# Nixie_board.net
KiCad netlist of a schematic drawn in EAGLE
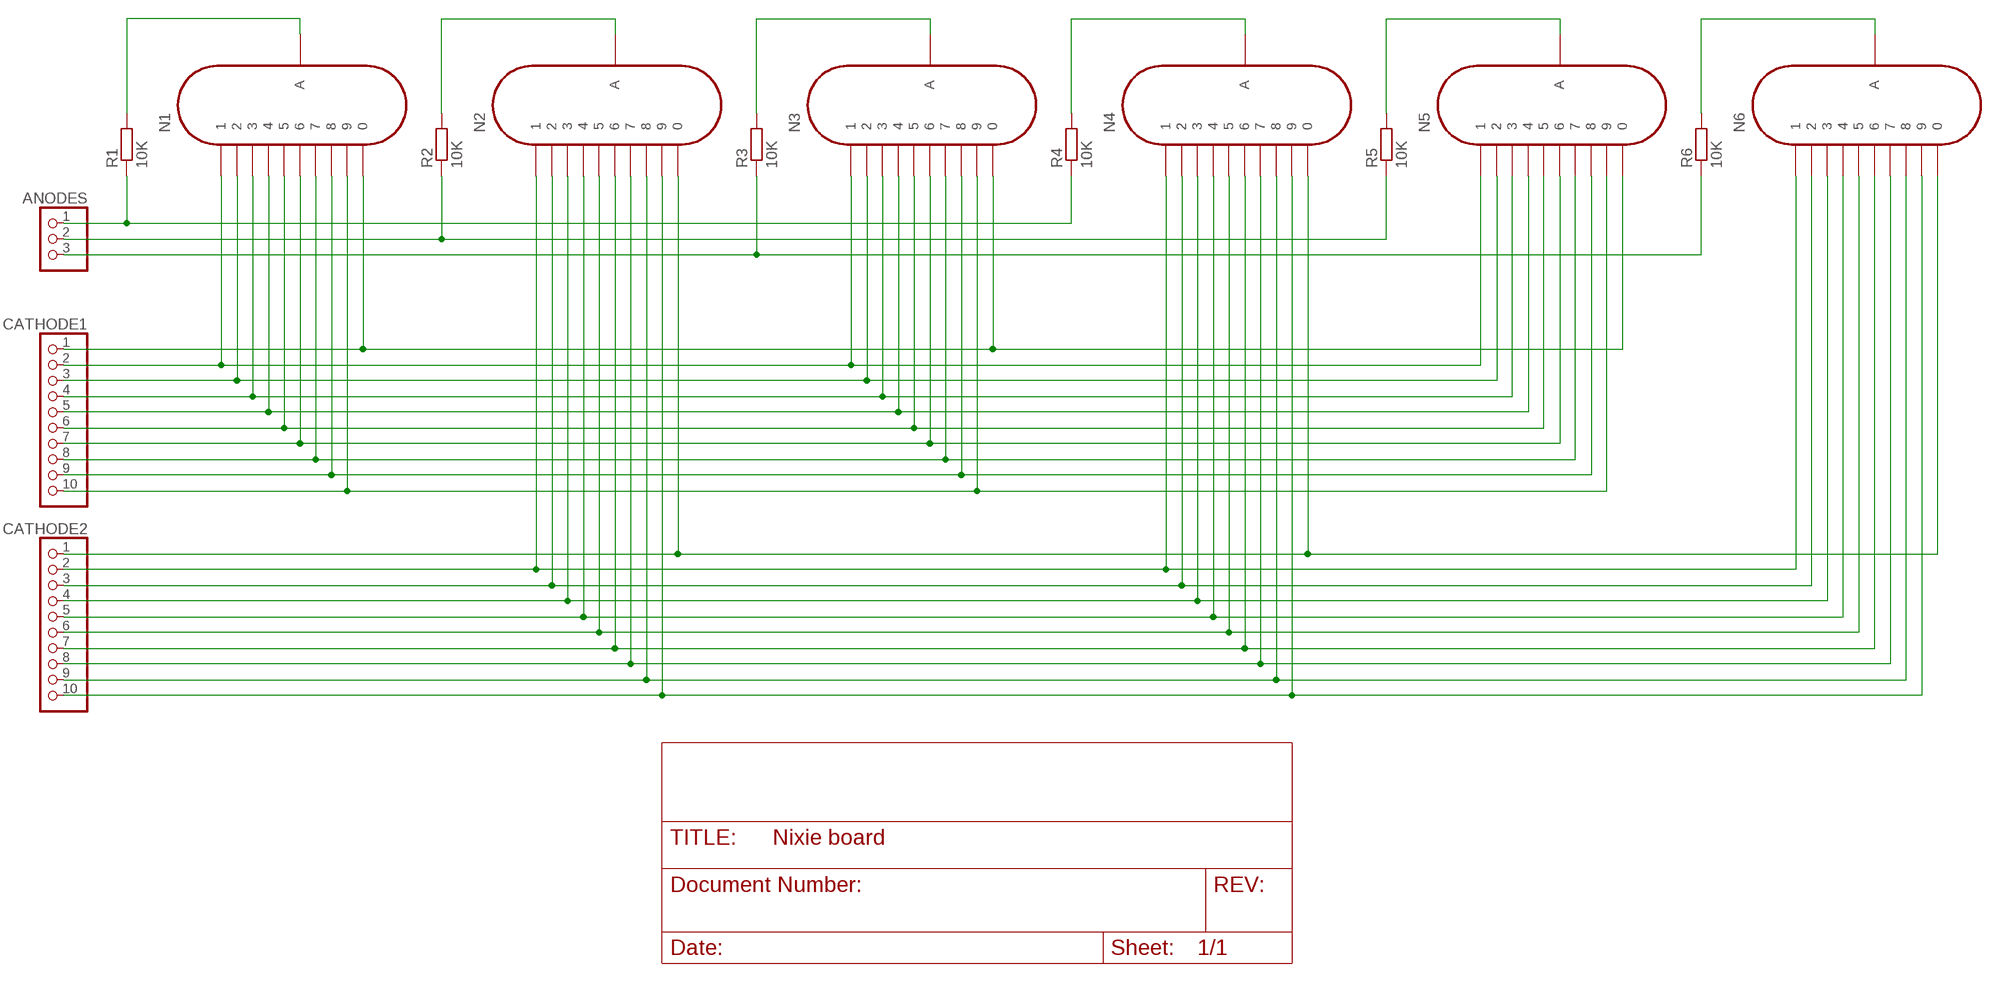
[diagram p0: schematic, sheet 1]

(export (version "E")
  (design (tool "Eeschema 10.0.6"))
  (components
    (comp (ref "ANODES")
      (value "PINHD-1X3")
      (footprint "eagle-import:1X03")
      (libsource (lib "eagle-import") (part "PINHD-1X3"))
    )
    (comp (ref "CATHODE1")
      (value "PINHD-1X10")
      (footprint "eagle-import:1X10")
      (libsource (lib "eagle-import") (part "PINHD-1X10"))
    )
    (comp (ref "CATHODE2")
      (value "PINHD-1X10")
      (footprint "eagle-import:1X10")
      (libsource (lib "eagle-import") (part "PINHD-1X10"))
    )
    (comp (ref "N1")
      (value "IN-12A")
      (footprint "eagle-import:IN-12")
      (libsource (lib "eagle-import") (part "IN-12A"))
    )
    (comp (ref "N2")
      (value "IN-12A")
      (footprint "eagle-import:IN-12")
      (libsource (lib "eagle-import") (part "IN-12A"))
    )
    (comp (ref "N3")
      (value "IN-12A")
      (footprint "eagle-import:IN-12")
      (libsource (lib "eagle-import") (part "IN-12A"))
    )
    (comp (ref "N4")
      (value "IN-12A")
      (footprint "eagle-import:IN-12")
      (libsource (lib "eagle-import") (part "IN-12A"))
    )
    (comp (ref "N5")
      (value "IN-12A")
      (footprint "eagle-import:IN-12")
      (libsource (lib "eagle-import") (part "IN-12A"))
    )
    (comp (ref "N6")
      (value "IN-12A")
      (footprint "eagle-import:IN-12")
      (libsource (lib "eagle-import") (part "IN-12A"))
    )
    (comp (ref "R1")
      (value "10K")
      (footprint "eagle-import:0207_10")
      (libsource (lib "eagle-import") (part "R-EU_0207/10"))
    )
    (comp (ref "R2")
      (value "10K")
      (footprint "eagle-import:0207_10")
      (libsource (lib "eagle-import") (part "R-EU_0207/10"))
    )
    (comp (ref "R3")
      (value "10K")
      (footprint "eagle-import:0207_10")
      (libsource (lib "eagle-import") (part "R-EU_0207/10"))
    )
    (comp (ref "R4")
      (value "10K")
      (footprint "eagle-import:0207_10")
      (libsource (lib "eagle-import") (part "R-EU_0207/10"))
    )
    (comp (ref "R5")
      (value "10K")
      (footprint "eagle-import:0207_10")
      (libsource (lib "eagle-import") (part "R-EU_0207/10"))
    )
    (comp (ref "R6")
      (value "10K")
      (footprint "eagle-import:0207_10")
      (libsource (lib "eagle-import") (part "R-EU_0207/10"))
    )
  )
  (nets
    (net (code "1") (name "Net-(ANODES-Pad1)") (class "Default")
      (node (ref "ANODES") (pin "1") (pinfunction "1_1") (pintype "passive"))
      (node (ref "R1") (pin "1") (pinfunction "1_1") (pintype "passive"))
      (node (ref "R4") (pin "1") (pinfunction "1_1") (pintype "passive"))
    )
    (net (code "2") (name "Net-(ANODES-Pad2)") (class "Default")
      (node (ref "ANODES") (pin "2") (pinfunction "2_2") (pintype "passive"))
      (node (ref "R2") (pin "1") (pinfunction "1_1") (pintype "passive"))
      (node (ref "R5") (pin "1") (pinfunction "1_1") (pintype "passive"))
    )
    (net (code "3") (name "Net-(ANODES-Pad3)") (class "Default")
      (node (ref "ANODES") (pin "3") (pinfunction "3_3") (pintype "passive"))
      (node (ref "R3") (pin "1") (pinfunction "1_1") (pintype "passive"))
      (node (ref "R6") (pin "1") (pinfunction "1_1") (pintype "passive"))
    )
    (net (code "4") (name "Net-(CATHODE1-Pad1)") (class "Default")
      (node (ref "CATHODE1") (pin "1") (pinfunction "1_1") (pintype "passive"))
      (node (ref "N1") (pin "0") (pinfunction "0_0") (pintype "bidirectional"))
      (node (ref "N3") (pin "0") (pinfunction "0_0") (pintype "bidirectional"))
      (node (ref "N5") (pin "0") (pinfunction "0_0") (pintype "bidirectional"))
    )
    (net (code "5") (name "Net-(CATHODE1-Pad2)") (class "Default")
      (node (ref "CATHODE1") (pin "2") (pinfunction "2_2") (pintype "passive"))
      (node (ref "N1") (pin "1") (pinfunction "1_1") (pintype "bidirectional"))
      (node (ref "N3") (pin "1") (pinfunction "1_1") (pintype "bidirectional"))
      (node (ref "N5") (pin "1") (pinfunction "1_1") (pintype "bidirectional"))
    )
    (net (code "6") (name "Net-(CATHODE1-Pad3)") (class "Default")
      (node (ref "CATHODE1") (pin "3") (pinfunction "3_3") (pintype "passive"))
      (node (ref "N1") (pin "2") (pinfunction "2_2") (pintype "bidirectional"))
      (node (ref "N3") (pin "2") (pinfunction "2_2") (pintype "bidirectional"))
      (node (ref "N5") (pin "2") (pinfunction "2_2") (pintype "bidirectional"))
    )
    (net (code "7") (name "Net-(CATHODE1-Pad4)") (class "Default")
      (node (ref "CATHODE1") (pin "4") (pinfunction "4_4") (pintype "passive"))
      (node (ref "N1") (pin "3") (pinfunction "3_3") (pintype "bidirectional"))
      (node (ref "N3") (pin "3") (pinfunction "3_3") (pintype "bidirectional"))
      (node (ref "N5") (pin "3") (pinfunction "3_3") (pintype "bidirectional"))
    )
    (net (code "8") (name "Net-(CATHODE1-Pad5)") (class "Default")
      (node (ref "CATHODE1") (pin "5") (pinfunction "5_5") (pintype "passive"))
      (node (ref "N1") (pin "4") (pinfunction "4_4") (pintype "bidirectional"))
      (node (ref "N3") (pin "4") (pinfunction "4_4") (pintype "bidirectional"))
      (node (ref "N5") (pin "4") (pinfunction "4_4") (pintype "bidirectional"))
    )
    (net (code "9") (name "Net-(CATHODE1-Pad6)") (class "Default")
      (node (ref "CATHODE1") (pin "6") (pinfunction "6_6") (pintype "passive"))
      (node (ref "N1") (pin "5") (pinfunction "5_5") (pintype "bidirectional"))
      (node (ref "N3") (pin "5") (pinfunction "5_5") (pintype "bidirectional"))
      (node (ref "N5") (pin "5") (pinfunction "5_5") (pintype "bidirectional"))
    )
    (net (code "10") (name "Net-(CATHODE1-Pad7)") (class "Default")
      (node (ref "CATHODE1") (pin "7") (pinfunction "7_7") (pintype "passive"))
      (node (ref "N1") (pin "6") (pinfunction "6_6") (pintype "bidirectional"))
      (node (ref "N3") (pin "6") (pinfunction "6_6") (pintype "bidirectional"))
      (node (ref "N5") (pin "6") (pinfunction "6_6") (pintype "bidirectional"))
    )
    (net (code "11") (name "Net-(CATHODE1-Pad8)") (class "Default")
      (node (ref "CATHODE1") (pin "8") (pinfunction "8_8") (pintype "passive"))
      (node (ref "N1") (pin "7") (pinfunction "7_7") (pintype "bidirectional"))
      (node (ref "N3") (pin "7") (pinfunction "7_7") (pintype "bidirectional"))
      (node (ref "N5") (pin "7") (pinfunction "7_7") (pintype "bidirectional"))
    )
    (net (code "12") (name "Net-(CATHODE1-Pad9)") (class "Default")
      (node (ref "CATHODE1") (pin "9") (pinfunction "9_9") (pintype "passive"))
      (node (ref "N1") (pin "8") (pinfunction "8_8") (pintype "bidirectional"))
      (node (ref "N3") (pin "8") (pinfunction "8_8") (pintype "bidirectional"))
      (node (ref "N5") (pin "8") (pinfunction "8_8") (pintype "bidirectional"))
    )
    (net (code "13") (name "Net-(CATHODE1-Pad10)") (class "Default")
      (node (ref "CATHODE1") (pin "10") (pinfunction "10_10") (pintype "passive"))
      (node (ref "N1") (pin "9") (pinfunction "9_9") (pintype "bidirectional"))
      (node (ref "N3") (pin "9") (pinfunction "9_9") (pintype "bidirectional"))
      (node (ref "N5") (pin "9") (pinfunction "9_9") (pintype "bidirectional"))
    )
    (net (code "14") (name "Net-(CATHODE2-Pad1)") (class "Default")
      (node (ref "CATHODE2") (pin "1") (pinfunction "1_1") (pintype "passive"))
      (node (ref "N2") (pin "0") (pinfunction "0_0") (pintype "bidirectional"))
      (node (ref "N4") (pin "0") (pinfunction "0_0") (pintype "bidirectional"))
      (node (ref "N6") (pin "0") (pinfunction "0_0") (pintype "bidirectional"))
    )
    (net (code "15") (name "Net-(CATHODE2-Pad2)") (class "Default")
      (node (ref "CATHODE2") (pin "2") (pinfunction "2_2") (pintype "passive"))
      (node (ref "N2") (pin "1") (pinfunction "1_1") (pintype "bidirectional"))
      (node (ref "N4") (pin "1") (pinfunction "1_1") (pintype "bidirectional"))
      (node (ref "N6") (pin "1") (pinfunction "1_1") (pintype "bidirectional"))
    )
    (net (code "16") (name "Net-(CATHODE2-Pad3)") (class "Default")
      (node (ref "CATHODE2") (pin "3") (pinfunction "3_3") (pintype "passive"))
      (node (ref "N2") (pin "2") (pinfunction "2_2") (pintype "bidirectional"))
      (node (ref "N4") (pin "2") (pinfunction "2_2") (pintype "bidirectional"))
      (node (ref "N6") (pin "2") (pinfunction "2_2") (pintype "bidirectional"))
    )
    (net (code "17") (name "Net-(CATHODE2-Pad4)") (class "Default")
      (node (ref "CATHODE2") (pin "4") (pinfunction "4_4") (pintype "passive"))
      (node (ref "N2") (pin "3") (pinfunction "3_3") (pintype "bidirectional"))
      (node (ref "N4") (pin "3") (pinfunction "3_3") (pintype "bidirectional"))
      (node (ref "N6") (pin "3") (pinfunction "3_3") (pintype "bidirectional"))
    )
    (net (code "18") (name "Net-(CATHODE2-Pad5)") (class "Default")
      (node (ref "CATHODE2") (pin "5") (pinfunction "5_5") (pintype "passive"))
      (node (ref "N2") (pin "4") (pinfunction "4_4") (pintype "bidirectional"))
      (node (ref "N4") (pin "4") (pinfunction "4_4") (pintype "bidirectional"))
      (node (ref "N6") (pin "4") (pinfunction "4_4") (pintype "bidirectional"))
    )
    (net (code "19") (name "Net-(CATHODE2-Pad6)") (class "Default")
      (node (ref "CATHODE2") (pin "6") (pinfunction "6_6") (pintype "passive"))
      (node (ref "N2") (pin "5") (pinfunction "5_5") (pintype "bidirectional"))
      (node (ref "N4") (pin "5") (pinfunction "5_5") (pintype "bidirectional"))
      (node (ref "N6") (pin "5") (pinfunction "5_5") (pintype "bidirectional"))
    )
    (net (code "20") (name "Net-(CATHODE2-Pad7)") (class "Default")
      (node (ref "CATHODE2") (pin "7") (pinfunction "7_7") (pintype "passive"))
      (node (ref "N2") (pin "6") (pinfunction "6_6") (pintype "bidirectional"))
      (node (ref "N4") (pin "6") (pinfunction "6_6") (pintype "bidirectional"))
      (node (ref "N6") (pin "6") (pinfunction "6_6") (pintype "bidirectional"))
    )
    (net (code "21") (name "Net-(CATHODE2-Pad8)") (class "Default")
      (node (ref "CATHODE2") (pin "8") (pinfunction "8_8") (pintype "passive"))
      (node (ref "N2") (pin "7") (pinfunction "7_7") (pintype "bidirectional"))
      (node (ref "N4") (pin "7") (pinfunction "7_7") (pintype "bidirectional"))
      (node (ref "N6") (pin "7") (pinfunction "7_7") (pintype "bidirectional"))
    )
    (net (code "22") (name "Net-(CATHODE2-Pad9)") (class "Default")
      (node (ref "CATHODE2") (pin "9") (pinfunction "9_9") (pintype "passive"))
      (node (ref "N2") (pin "8") (pinfunction "8_8") (pintype "bidirectional"))
      (node (ref "N4") (pin "8") (pinfunction "8_8") (pintype "bidirectional"))
      (node (ref "N6") (pin "8") (pinfunction "8_8") (pintype "bidirectional"))
    )
    (net (code "23") (name "Net-(CATHODE2-Pad10)") (class "Default")
      (node (ref "CATHODE2") (pin "10") (pinfunction "10_10") (pintype "passive"))
      (node (ref "N2") (pin "9") (pinfunction "9_9") (pintype "bidirectional"))
      (node (ref "N4") (pin "9") (pinfunction "9_9") (pintype "bidirectional"))
      (node (ref "N6") (pin "9") (pinfunction "9_9") (pintype "bidirectional"))
    )
    (net (code "24") (name "Net-(N1-PadA)") (class "Default")
      (node (ref "N1") (pin "A") (pinfunction "A_A") (pintype "bidirectional"))
      (node (ref "R1") (pin "2") (pinfunction "2_2") (pintype "passive"))
    )
    (net (code "25") (name "Net-(N2-PadA)") (class "Default")
      (node (ref "N2") (pin "A") (pinfunction "A_A") (pintype "bidirectional"))
      (node (ref "R2") (pin "2") (pinfunction "2_2") (pintype "passive"))
    )
    (net (code "26") (name "Net-(N3-PadA)") (class "Default")
      (node (ref "N3") (pin "A") (pinfunction "A_A") (pintype "bidirectional"))
      (node (ref "R3") (pin "2") (pinfunction "2_2") (pintype "passive"))
    )
    (net (code "27") (name "Net-(N4-PadA)") (class "Default")
      (node (ref "N4") (pin "A") (pinfunction "A_A") (pintype "bidirectional"))
      (node (ref "R4") (pin "2") (pinfunction "2_2") (pintype "passive"))
    )
    (net (code "28") (name "Net-(N5-PadA)") (class "Default")
      (node (ref "N5") (pin "A") (pinfunction "A_A") (pintype "bidirectional"))
      (node (ref "R5") (pin "2") (pinfunction "2_2") (pintype "passive"))
    )
    (net (code "29") (name "Net-(N6-PadA)") (class "Default")
      (node (ref "N6") (pin "A") (pinfunction "A_A") (pintype "bidirectional"))
      (node (ref "R6") (pin "2") (pinfunction "2_2") (pintype "passive"))
    )
  )
)
